# RF.net
KiCad netlist of a schematic drawn in Altium Designer
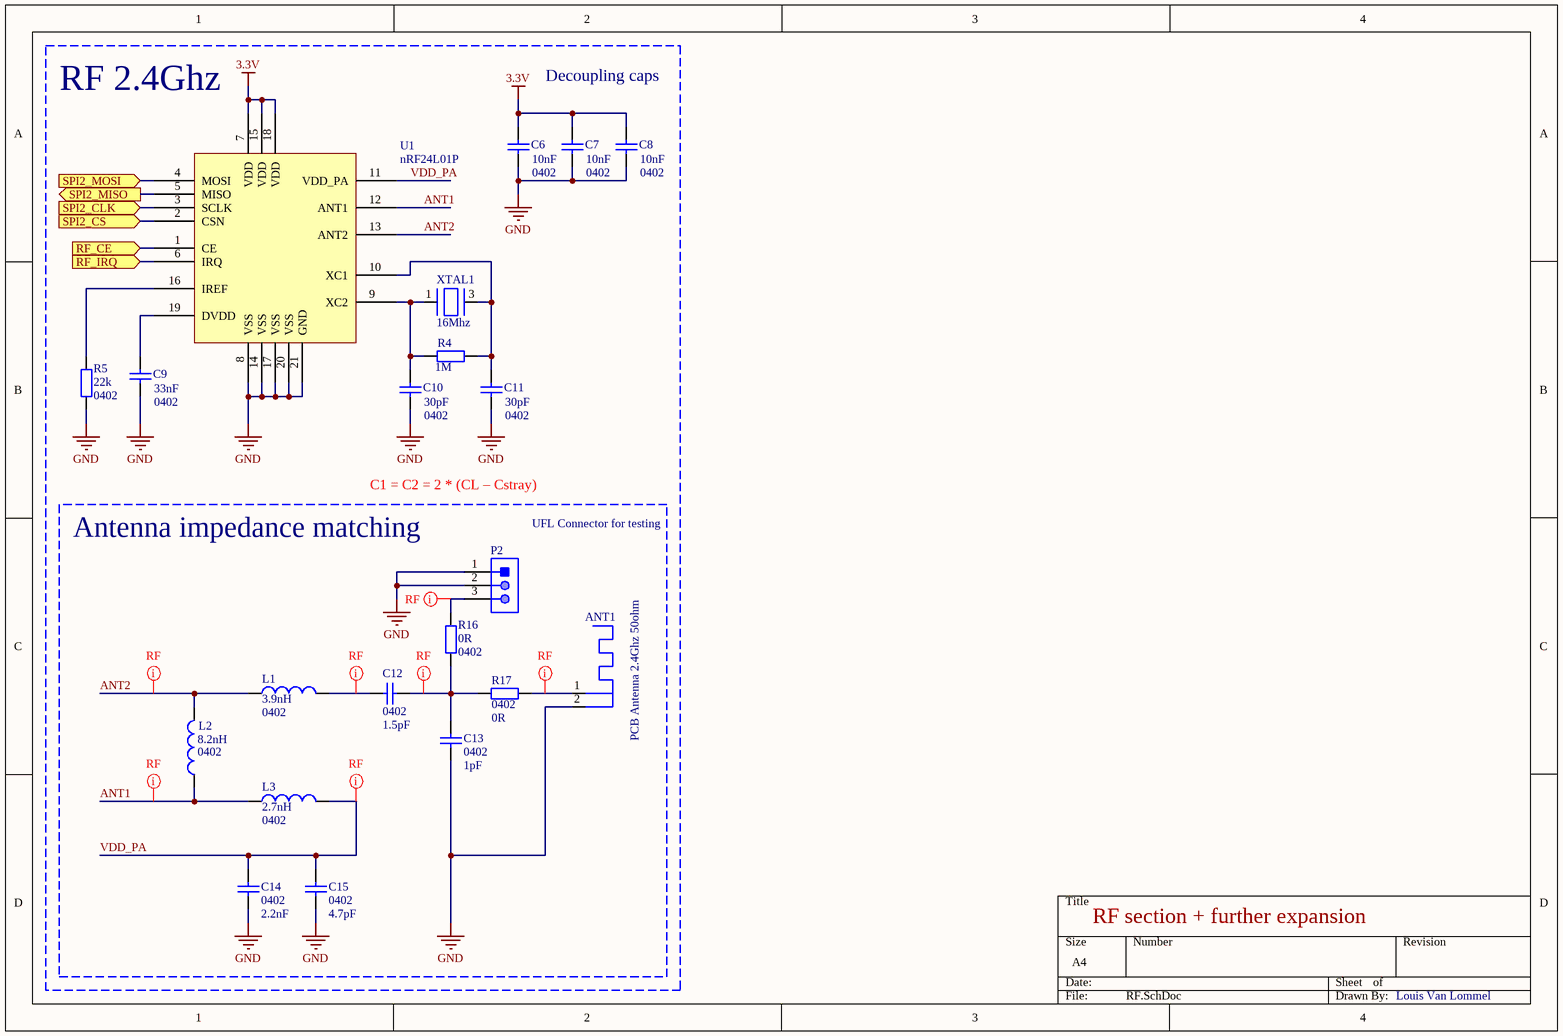
[diagram p0: RF.SchDoc]

(export (version "E")
  (design (tool "Eeschema 10.0.6"))
  (components
    (comp (ref "ANT1")
      (value "PCB Antenna 2.4Ghz 50ohm")
      (footprint "2.4Ghz Antenna")
      (libsource (lib "PE2_Schematics") (part "Antenna 2.4Ghz"))
    )
    (comp (ref "C6")
      (value "0402")
      (footprint "CAP_0402")
      (description "Capacitor")
      (fields (field (name "ALTIUM_VALUE") "10nF") (field (name "PUBLISHER") "Altium Limited"))
      (libsource (lib "Miscellaneous Devices") (part "Cap"))
    )
    (comp (ref "C7")
      (value "0402")
      (footprint "CAP_0402")
      (description "Capacitor")
      (fields (field (name "ALTIUM_VALUE") "10nF") (field (name "PUBLISHER") "Altium Limited"))
      (libsource (lib "Miscellaneous Devices") (part "Cap"))
    )
    (comp (ref "C8")
      (value "0402")
      (footprint "CAP_0402")
      (description "Capacitor")
      (fields (field (name "ALTIUM_VALUE") "10nF") (field (name "PUBLISHER") "Altium Limited"))
      (libsource (lib "Miscellaneous Devices") (part "Cap"))
    )
    (comp (ref "C9")
      (value "0402")
      (footprint "CAP_0402")
      (description "Capacitor")
      (fields (field (name "ALTIUM_VALUE") "33nF") (field (name "PUBLISHER") "Altium Limited"))
      (libsource (lib "Miscellaneous Devices") (part "Cap"))
    )
    (comp (ref "C10")
      (value "0402")
      (footprint "CAP_0402")
      (description "Capacitor")
      (fields (field (name "ALTIUM_VALUE") "30pF") (field (name "PUBLISHER") "Altium Limited"))
      (libsource (lib "Miscellaneous Devices") (part "Cap"))
    )
    (comp (ref "C11")
      (value "0402")
      (footprint "CAP_0402")
      (description "Capacitor")
      (fields (field (name "ALTIUM_VALUE") "30pF") (field (name "PUBLISHER") "Altium Limited"))
      (libsource (lib "Miscellaneous Devices") (part "Cap"))
    )
    (comp (ref "C12")
      (value "0402")
      (footprint "CAP_0402")
      (description "Capacitor")
      (fields (field (name "ALTIUM_VALUE") "1.5pF") (field (name "PUBLISHER") "Altium Limited"))
      (libsource (lib "Miscellaneous Devices") (part "Cap"))
    )
    (comp (ref "C13")
      (value "0402")
      (footprint "CAP_0402")
      (description "Capacitor")
      (fields (field (name "ALTIUM_VALUE") "1pF") (field (name "PUBLISHER") "Altium Limited"))
      (libsource (lib "Miscellaneous Devices") (part "Cap"))
    )
    (comp (ref "C14")
      (value "0402")
      (footprint "CAP_0402")
      (description "Capacitor")
      (fields (field (name "ALTIUM_VALUE") "2.2nF") (field (name "PUBLISHER") "Altium Limited"))
      (libsource (lib "Miscellaneous Devices") (part "Cap"))
    )
    (comp (ref "C15")
      (value "0402")
      (footprint "CAP_0402")
      (description "Capacitor")
      (fields (field (name "ALTIUM_VALUE") "4.7pF") (field (name "PUBLISHER") "Altium Limited"))
      (libsource (lib "Miscellaneous Devices") (part "Cap"))
    )
    (comp (ref "L1")
      (value "0402")
      (footprint "IND_0402")
      (description "Inductor")
      (fields (field (name "ALTIUM_VALUE") "3.9nH") (field (name "PUBLISHER") "Altium Limited"))
      (libsource (lib "Miscellaneous Devices") (part "Inductor"))
    )
    (comp (ref "L2")
      (value "0402")
      (footprint "IND_0402")
      (description "Inductor")
      (fields (field (name "ALTIUM_VALUE") "8.2nH") (field (name "PUBLISHER") "Altium Limited"))
      (libsource (lib "Miscellaneous Devices") (part "Inductor"))
    )
    (comp (ref "L3")
      (value "0402")
      (footprint "IND_0402")
      (description "Inductor")
      (fields (field (name "ALTIUM_VALUE") "2.7nH") (field (name "PUBLISHER") "Altium Limited"))
      (libsource (lib "Miscellaneous Devices") (part "Inductor"))
    )
    (comp (ref "P2")
      (value "~")
      (footprint "HRS-U.FL-R-SMT-3_V")
      (description "Ultra Small Coaxial Connector, 6 GHz, -40 to 90 degC, 3-Pin SMD, RoHS, Bulk")
      (fields (field (name "MANUFACTURER") "Hirose Electric"))
      (libsource (lib "Altium Content Vault") (part "CN-1P-M-R3"))
    )
    (comp (ref "R4")
      (value "1M")
      (footprint "RES_0402")
      (description "Resistor")
      (fields (field (name "PUBLISHER") "Altium Limited"))
      (libsource (lib "Miscellaneous Devices") (part "Res2"))
    )
    (comp (ref "R5")
      (value "0402")
      (footprint "RES_0402")
      (description "Resistor")
      (fields (field (name "ALTIUM_VALUE") "22k") (field (name "PUBLISHER") "Altium Limited"))
      (libsource (lib "") (part "Res2_1"))
    )
    (comp (ref "R16")
      (value "0402")
      (footprint "RES_0402")
      (description "Resistor")
      (fields (field (name "ALTIUM_VALUE") "0R") (field (name "PUBLISHER") "Altium Limited"))
      (libsource (lib "") (part "Res2_1"))
    )
    (comp (ref "R17")
      (value "0402")
      (footprint "RES_0402")
      (description "Resistor")
      (fields (field (name "ALTIUM_VALUE") "0R") (field (name "PUBLISHER") "Altium Limited"))
      (libsource (lib "Miscellaneous Devices") (part "Res2"))
    )
    (comp (ref "U1")
      (value "nRF24L01P")
      (footprint "QFN20 4x4")
      (description "Single Chip Transceiver, 2.4 GHz, 60 mW, 1.9 to 3.6 V, -40 to 85 degC, 20-Pin QFN, RoHS, Tray")
      (libsource (lib "PE2_Schematics") (part "nRF24L01P"))
    )
    (comp (ref "XTAL1")
      (value "16Mhz")
      (footprint "16Mhz_Crystal")
      (description "Crystal, 16 MHz, SMD, 3.2mm x 2.5mm, 30 ppm, 18 pF, 30 ppm, 7M")
      (libsource (lib "AP2112") (part "Crystal"))
    )
  )
  (nets
    (net (code "1") (name "/ANT1") (class "Default")
      (node (ref "L2") (pin "1") (pinfunction "1_1") (pintype "passive"))
      (node (ref "L3") (pin "1") (pinfunction "1_1") (pintype "passive"))
      (node (ref "U1") (pin "12") (pinfunction "ANT1_12") (pintype "passive"))
    )
    (net (code "2") (name "/ANT2") (class "Default")
      (node (ref "L1") (pin "1") (pinfunction "1_1") (pintype "passive"))
      (node (ref "L2") (pin "2") (pinfunction "2_2") (pintype "passive"))
      (node (ref "U1") (pin "13") (pinfunction "ANT2_13") (pintype "passive"))
    )
    (net (code "3") (name "/RF_CE") (class "Default")
      (node (ref "U1") (pin "1") (pinfunction "CE_1") (pintype "passive"))
    )
    (net (code "4") (name "/RF_IRQ") (class "Default")
      (node (ref "U1") (pin "6") (pinfunction "IRQ_6") (pintype "passive"))
    )
    (net (code "5") (name "/SPI2_CLK") (class "Default")
      (node (ref "U1") (pin "3") (pinfunction "SCLK_3") (pintype "passive"))
    )
    (net (code "6") (name "/SPI2_CS") (class "Default")
      (node (ref "U1") (pin "2") (pinfunction "CSN_2") (pintype "passive"))
    )
    (net (code "7") (name "/SPI2_MISO") (class "Default")
      (node (ref "U1") (pin "5") (pinfunction "MISO_5") (pintype "passive"))
    )
    (net (code "8") (name "/SPI2_MOSI") (class "Default")
      (node (ref "U1") (pin "4") (pinfunction "MOSI_4") (pintype "passive"))
    )
    (net (code "9") (name "/VDD_PA") (class "Default")
      (node (ref "C14") (pin "1") (pinfunction "1_1") (pintype "passive"))
      (node (ref "C15") (pin "1") (pinfunction "1_1") (pintype "passive"))
      (node (ref "L3") (pin "2") (pinfunction "2_2") (pintype "passive"))
      (node (ref "U1") (pin "11") (pinfunction "VDD_PA_11") (pintype "passive"))
    )
    (net (code "10") (name "3.3V") (class "Default")
      (node (ref "C6") (pin "2") (pinfunction "2_2") (pintype "passive"))
      (node (ref "C7") (pin "2") (pinfunction "2_2") (pintype "passive"))
      (node (ref "C8") (pin "2") (pinfunction "2_2") (pintype "passive"))
      (node (ref "U1") (pin "15") (pinfunction "VDD_15") (pintype "passive"))
      (node (ref "U1") (pin "18") (pinfunction "VDD_18") (pintype "passive"))
      (node (ref "U1") (pin "7") (pinfunction "VDD_7") (pintype "passive"))
    )
    (net (code "11") (name "GND") (class "Default")
      (node (ref "ANT1") (pin "2") (pinfunction "GND_2") (pintype "passive"))
      (node (ref "C10") (pin "1") (pinfunction "1_1") (pintype "passive"))
      (node (ref "C11") (pin "1") (pinfunction "1_1") (pintype "passive"))
      (node (ref "C13") (pin "2") (pinfunction "2_2") (pintype "passive"))
      (node (ref "C14") (pin "2") (pinfunction "2_2") (pintype "passive"))
      (node (ref "C15") (pin "2") (pinfunction "2_2") (pintype "passive"))
      (node (ref "C6") (pin "1") (pinfunction "1_1") (pintype "passive"))
      (node (ref "C7") (pin "1") (pinfunction "1_1") (pintype "passive"))
      (node (ref "C8") (pin "1") (pinfunction "1_1") (pintype "passive"))
      (node (ref "C9") (pin "1") (pinfunction "1_1") (pintype "passive"))
      (node (ref "P2") (pin "1") (pinfunction "1_1") (pintype "passive"))
      (node (ref "P2") (pin "2") (pinfunction "2_2") (pintype "passive"))
      (node (ref "R5") (pin "2") (pinfunction "2_2") (pintype "passive"))
      (node (ref "U1") (pin "14") (pinfunction "VSS_14") (pintype "passive"))
      (node (ref "U1") (pin "17") (pinfunction "VSS_17") (pintype "passive"))
      (node (ref "U1") (pin "20") (pinfunction "VSS_20") (pintype "passive"))
      (node (ref "U1") (pin "21") (pinfunction "GND_21") (pintype "passive"))
      (node (ref "U1") (pin "8") (pinfunction "VSS_8") (pintype "passive"))
    )
    (net (code "12") (name "Net-(ANT1-RF)") (class "Default")
      (node (ref "ANT1") (pin "1") (pinfunction "RF_1") (pintype "passive"))
      (node (ref "R17") (pin "2") (pinfunction "2_2") (pintype "passive"))
    )
    (net (code "13") (name "Net-(C12-Pad1)") (class "Default")
      (node (ref "C12") (pin "1") (pinfunction "1_1") (pintype "passive"))
      (node (ref "C13") (pin "1") (pinfunction "1_1") (pintype "passive"))
      (node (ref "R16") (pin "2") (pinfunction "2_2") (pintype "passive"))
      (node (ref "R17") (pin "1") (pinfunction "1_1") (pintype "passive"))
    )
    (net (code "14") (name "Net-(C12-Pad2)") (class "Default")
      (node (ref "C12") (pin "2") (pinfunction "2_2") (pintype "passive"))
      (node (ref "L1") (pin "2") (pinfunction "2_2") (pintype "passive"))
    )
    (net (code "15") (name "Net-(P2-Pad3)") (class "Default")
      (node (ref "P2") (pin "3") (pinfunction "3_3") (pintype "passive"))
      (node (ref "R16") (pin "1") (pinfunction "1_1") (pintype "passive"))
    )
    (net (code "16") (name "Net-(U1-DVDD)") (class "Default")
      (node (ref "C9") (pin "2") (pinfunction "2_2") (pintype "passive"))
      (node (ref "U1") (pin "19") (pinfunction "DVDD_19") (pintype "passive"))
    )
    (net (code "17") (name "Net-(U1-IREF)") (class "Default")
      (node (ref "R5") (pin "1") (pinfunction "1_1") (pintype "passive"))
      (node (ref "U1") (pin "16") (pinfunction "IREF_16") (pintype "passive"))
    )
    (net (code "18") (name "Net-(U1-XC1)") (class "Default")
      (node (ref "C11") (pin "2") (pinfunction "2_2") (pintype "passive"))
      (node (ref "R4") (pin "2") (pinfunction "2_2") (pintype "passive"))
      (node (ref "U1") (pin "10") (pinfunction "XC1_10") (pintype "passive"))
      (node (ref "XTAL1") (pin "3") (pinfunction "3_3") (pintype "passive"))
    )
    (net (code "19") (name "Net-(U1-XC2)") (class "Default")
      (node (ref "C10") (pin "2") (pinfunction "2_2") (pintype "passive"))
      (node (ref "R4") (pin "1") (pinfunction "1_1") (pintype "passive"))
      (node (ref "U1") (pin "9") (pinfunction "XC2_9") (pintype "passive"))
      (node (ref "XTAL1") (pin "1") (pinfunction "1_1") (pintype "passive"))
    )
  )
)
